# Shield.net
KiCad netlist of a schematic drawn in Altium Designer
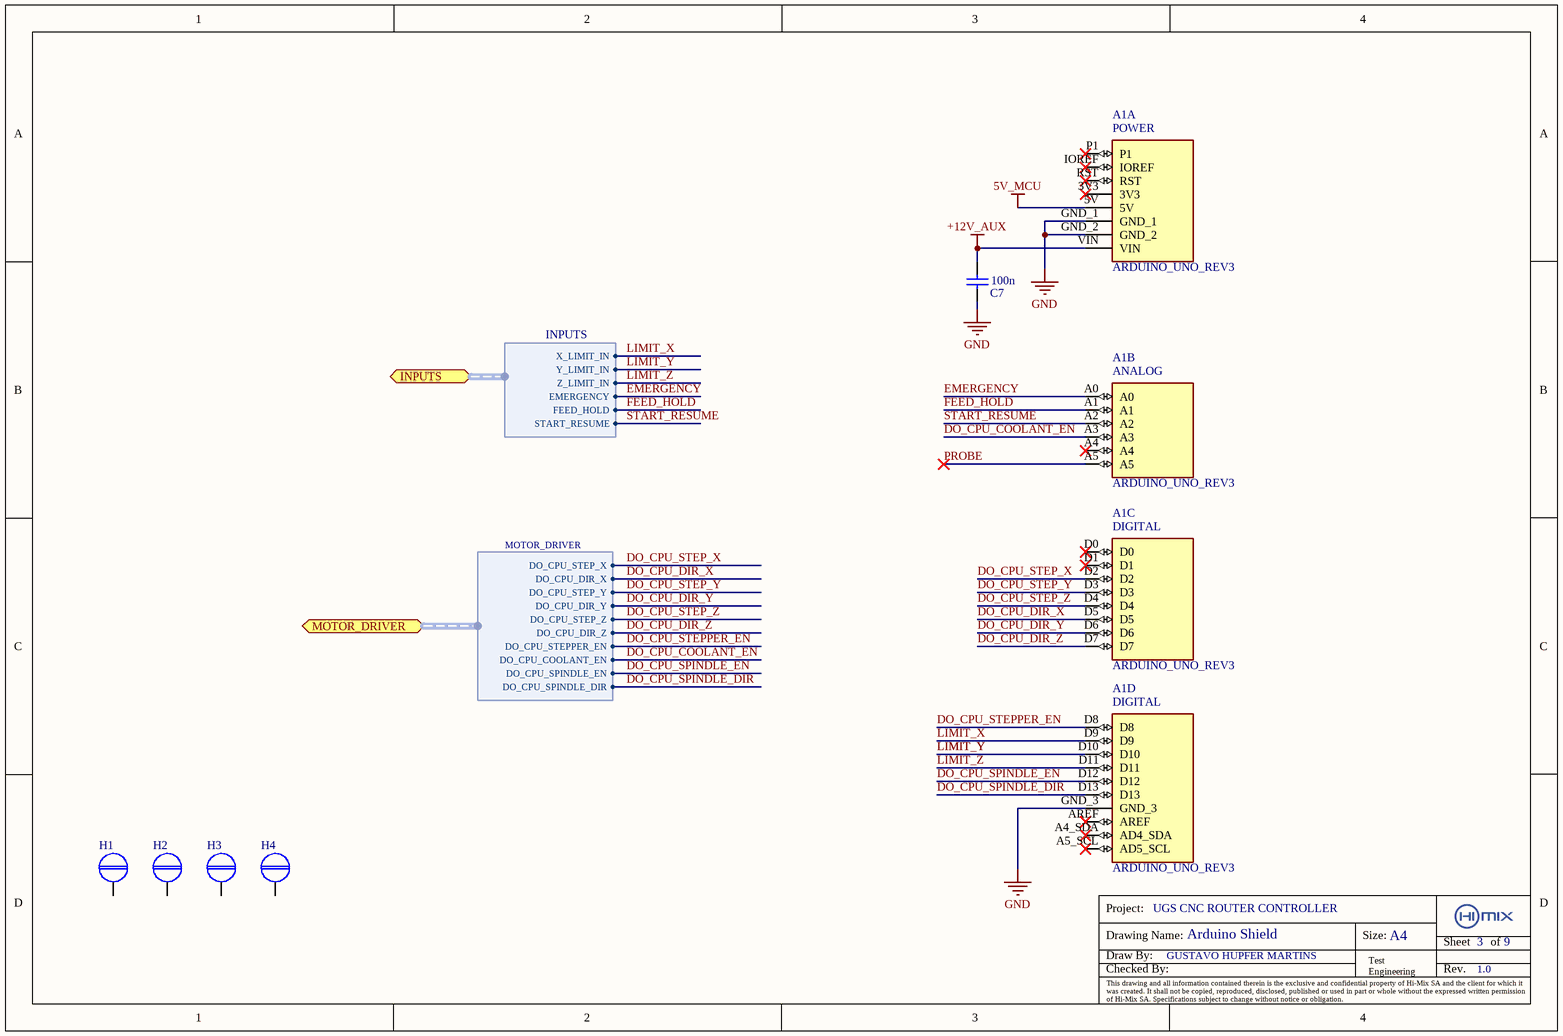
[diagram p0: Shield.SchDoc]

(export (version "E")
  (design (tool "Eeschema 10.0.6"))
  (components
    (comp (ref "A1")
      (value "ARDUINO_UNO_REV3")
      (footprint "ARDUINO_ARDUINO_UNO_REV3")
      (description "Microcontroller board based on the ATmega328P.")
      (fields (field (name "MF") "Arduino") (field (name "MP") "ARDUINO UNO REV3"))
      (libsource (lib "ARDUINO_UNO_REV3") (part "ARDUINO_UNO_REV3"))
    )
    (comp (ref "C7")
      (value "100n")
      (footprint "SMT0805_M")
      (description "Capacitor")
      (fields (field (name "PUBLISHER") "Altium Limited"))
      (libsource (lib "Misc") (part "Capacitor"))
    )
    (comp (ref "H1") (value "Hole") (footprint "Hole 3.2mm x 6.5mm") (libsource (lib "Misc") (part "Hole")))
    (comp (ref "H2") (value "Hole") (footprint "Hole 3.2mm x 6.5mm") (libsource (lib "Misc") (part "Hole")))
    (comp (ref "H3") (value "Hole") (footprint "Hole 3.2mm x 6.5mm") (libsource (lib "Misc") (part "Hole")))
    (comp (ref "H4") (value "Hole") (footprint "Hole 3.2mm x 6.5mm") (libsource (lib "Misc") (part "Hole")))
  )
  (nets
    (net (code "3") (name "+12V_AUX") (class "Default")
      (node (ref "A1") (pin "VIN") (pinfunction "VIN_VIN") (pintype "power_in"))
      (node (ref "C7") (pin "2") (pinfunction "2_2") (pintype "passive"))
    )
    (net (code "4") (name "/DO_CPU_COOLANT_EN") (class "Default")
      (node (ref "A1") (pin "A3") (pinfunction "A3_A3") (pintype "bidirectional"))
    )
    (net (code "5") (name "/DO_CPU_DIR_X") (class "Default")
      (node (ref "A1") (pin "D5") (pinfunction "D5_D5") (pintype "bidirectional"))
    )
    (net (code "6") (name "/DO_CPU_DIR_Y") (class "Default")
      (node (ref "A1") (pin "D6") (pinfunction "D6_D6") (pintype "bidirectional"))
    )
    (net (code "7") (name "/DO_CPU_DIR_Z") (class "Default")
      (node (ref "A1") (pin "D7") (pinfunction "D7_D7") (pintype "bidirectional"))
    )
    (net (code "8") (name "/DO_CPU_SPINDLE_DIR") (class "Default")
      (node (ref "A1") (pin "D13") (pinfunction "D13_D13") (pintype "bidirectional"))
    )
    (net (code "9") (name "/DO_CPU_SPINDLE_EN") (class "Default")
      (node (ref "A1") (pin "D12") (pinfunction "D12_D12") (pintype "bidirectional"))
    )
    (net (code "10") (name "/DO_CPU_STEPPER_EN") (class "Default")
      (node (ref "A1") (pin "D8") (pinfunction "D8_D8") (pintype "bidirectional"))
    )
    (net (code "11") (name "/DO_CPU_STEP_X") (class "Default")
      (node (ref "A1") (pin "D2") (pinfunction "D2_D2") (pintype "bidirectional"))
    )
    (net (code "12") (name "/DO_CPU_STEP_Y") (class "Default")
      (node (ref "A1") (pin "D3") (pinfunction "D3_D3") (pintype "bidirectional"))
    )
    (net (code "13") (name "/DO_CPU_STEP_Z") (class "Default")
      (node (ref "A1") (pin "D4") (pinfunction "D4_D4") (pintype "bidirectional"))
    )
    (net (code "14") (name "/EMERGENCY") (class "Default")
      (node (ref "A1") (pin "A0") (pinfunction "A0_A0") (pintype "bidirectional"))
    )
    (net (code "15") (name "/FEED_HOLD") (class "Default")
      (node (ref "A1") (pin "A1") (pinfunction "A1_A1") (pintype "bidirectional"))
    )
    (net (code "16") (name "/LIMIT_X") (class "Default")
      (node (ref "A1") (pin "D9") (pinfunction "D9_D9") (pintype "bidirectional"))
    )
    (net (code "17") (name "/LIMIT_Y") (class "Default")
      (node (ref "A1") (pin "D10") (pinfunction "D10_D10") (pintype "bidirectional"))
    )
    (net (code "18") (name "/LIMIT_Z") (class "Default")
      (node (ref "A1") (pin "D11") (pinfunction "D11_D11") (pintype "bidirectional"))
    )
    (net (code "19") (name "/PROBE") (class "Default")
      (node (ref "A1") (pin "A5") (pinfunction "A5_A5") (pintype "bidirectional+no_connect"))
    )
    (net (code "20") (name "/START_RESUME") (class "Default")
      (node (ref "A1") (pin "A2") (pinfunction "A2_A2") (pintype "bidirectional"))
    )
    (net (code "23") (name "5V_MCU") (class "Default")
      (node (ref "A1") (pin "5V") (pinfunction "5V_5V") (pintype "power_in"))
    )
    (net (code "24") (name "GND") (class "Default")
      (node (ref "A1") (pin "GND_1") (pinfunction "GND_1_GND_1") (pintype "power_in"))
      (node (ref "A1") (pin "GND_2") (pinfunction "GND_2_GND_2") (pintype "power_in"))
      (node (ref "A1") (pin "GND_3") (pinfunction "GND_3_GND_3") (pintype "power_in"))
      (node (ref "C7") (pin "1") (pinfunction "1_1") (pintype "passive"))
    )
    (net (code "25") (name "unconnected-(A1-Pad3V3)") (class "Default")
      (node (ref "A1") (pin "3V3") (pinfunction "3V3_3V3") (pintype "power_in+no_connect"))
    )
    (net (code "26") (name "unconnected-(A1-PadA4)") (class "Default")
      (node (ref "A1") (pin "A4") (pinfunction "A4_A4") (pintype "bidirectional+no_connect"))
    )
    (net (code "27") (name "unconnected-(A1-PadAREF)") (class "Default")
      (node (ref "A1") (pin "AREF") (pinfunction "AREF_AREF") (pintype "bidirectional+no_connect"))
    )
    (net (code "28") (name "unconnected-(A1-PadD0)") (class "Default")
      (node (ref "A1") (pin "D0") (pinfunction "D0_D0") (pintype "bidirectional+no_connect"))
    )
    (net (code "29") (name "unconnected-(A1-PadD1)") (class "Default")
      (node (ref "A1") (pin "D1") (pinfunction "D1_D1") (pintype "bidirectional+no_connect"))
    )
    (net (code "30") (name "unconnected-(A1-PadIOREF)") (class "Default")
      (node (ref "A1") (pin "IOREF") (pinfunction "IOREF_IOREF") (pintype "bidirectional+no_connect"))
    )
    (net (code "31") (name "unconnected-(A1-PadP1)") (class "Default")
      (node (ref "A1") (pin "P1") (pinfunction "P1_P1") (pintype "bidirectional+no_connect"))
    )
    (net (code "32") (name "unconnected-(A1-PadRST)") (class "Default")
      (node (ref "A1") (pin "RST") (pinfunction "RST_RST") (pintype "bidirectional+no_connect"))
    )
    (net (code "33") (name "unconnected-(A1D-AD4_SDA-PadA4_SDA)") (class "Default")
      (node (ref "A1") (pin "A4_SDA") (pinfunction "AD4_SDA_A4_SDA") (pintype "bidirectional+no_connect"))
    )
    (net (code "34") (name "unconnected-(A1D-AD5_SCL-PadA5_SCL)") (class "Default")
      (node (ref "A1") (pin "A5_SCL") (pinfunction "AD5_SCL_A5_SCL") (pintype "bidirectional+no_connect"))
    )
    (net (code "35") (name "unconnected-(H1-Pad1)") (class "Default")
      (node (ref "H1") (pin "1") (pintype "passive"))
    )
    (net (code "36") (name "unconnected-(H2-Pad1)") (class "Default")
      (node (ref "H2") (pin "1") (pintype "passive"))
    )
    (net (code "37") (name "unconnected-(H3-Pad1)") (class "Default")
      (node (ref "H3") (pin "1") (pintype "passive"))
    )
    (net (code "38") (name "unconnected-(H4-Pad1)") (class "Default")
      (node (ref "H4") (pin "1") (pintype "passive"))
    )
  )
)
